# Breadboard_Pot.net
KiCad netlist of a schematic drawn in Altium Designer
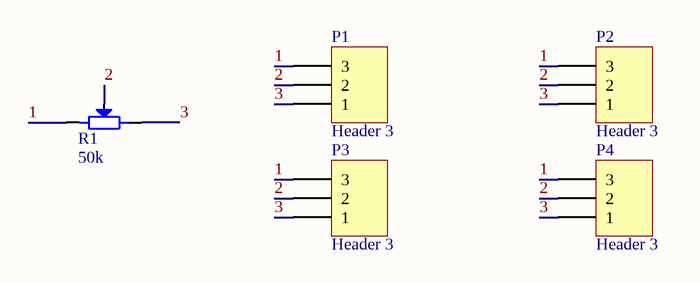
[diagram p0: Breadboard_Pot.SchDoc]

(export (version "E")
  (design (tool "Eeschema 10.0.6"))
  (components
    (comp (ref "P1")
      (value "Header 3")
      (footprint "HDR1X3")
      (description "Header, 3-Pin")
      (fields (field (name "PUBLISHER") "Altium Limited"))
      (libsource (lib "MH_THU VIEN CHUAN 01-11-2014") (part "Header 3"))
    )
    (comp (ref "P2")
      (value "Header 3")
      (footprint "HDR1X3")
      (description "Header, 3-Pin")
      (fields (field (name "PUBLISHER") "Altium Limited"))
      (libsource (lib "MH_THU VIEN CHUAN 01-11-2014") (part "Header 3"))
    )
    (comp (ref "P3")
      (value "Header 3")
      (footprint "HDR1X3")
      (description "Header, 3-Pin")
      (fields (field (name "PUBLISHER") "Altium Limited"))
      (libsource (lib "MH_THU VIEN CHUAN 01-11-2014") (part "Header 3"))
    )
    (comp (ref "P4")
      (value "Header 3")
      (footprint "HDR1X3")
      (description "Header, 3-Pin")
      (fields (field (name "PUBLISHER") "Altium Limited"))
      (libsource (lib "MH_THU VIEN CHUAN 01-11-2014") (part "Header 3"))
    )
    (comp (ref "R1") (value "50k") (footprint "RV09") (libsource (lib "RomHunter") (part "POT")))
  )
  (nets
    (net (code "1") (name "/1") (class "Default")
      (node (ref "P1") (pin "3") (pinfunction "3_3") (pintype "passive"))
      (node (ref "P2") (pin "3") (pinfunction "3_3") (pintype "passive"))
      (node (ref "P3") (pin "3") (pinfunction "3_3") (pintype "passive"))
      (node (ref "P4") (pin "3") (pinfunction "3_3") (pintype "passive"))
      (node (ref "R1") (pin "1") (pinfunction "1_1") (pintype "passive"))
    )
    (net (code "2") (name "/2") (class "Default")
      (node (ref "P1") (pin "2") (pinfunction "2_2") (pintype "passive"))
      (node (ref "P2") (pin "2") (pinfunction "2_2") (pintype "passive"))
      (node (ref "P3") (pin "2") (pinfunction "2_2") (pintype "passive"))
      (node (ref "P4") (pin "2") (pinfunction "2_2") (pintype "passive"))
      (node (ref "R1") (pin "2") (pinfunction "W_2") (pintype "passive"))
    )
    (net (code "3") (name "/3") (class "Default")
      (node (ref "P1") (pin "1") (pinfunction "1_1") (pintype "passive"))
      (node (ref "P2") (pin "1") (pinfunction "1_1") (pintype "passive"))
      (node (ref "P3") (pin "1") (pinfunction "1_1") (pintype "passive"))
      (node (ref "P4") (pin "1") (pinfunction "1_1") (pintype "passive"))
      (node (ref "R1") (pin "3") (pinfunction "3_3") (pintype "passive"))
    )
  )
)
